# Overcurrent_Protection.net
KiCad netlist of a schematic drawn in Altium Designer
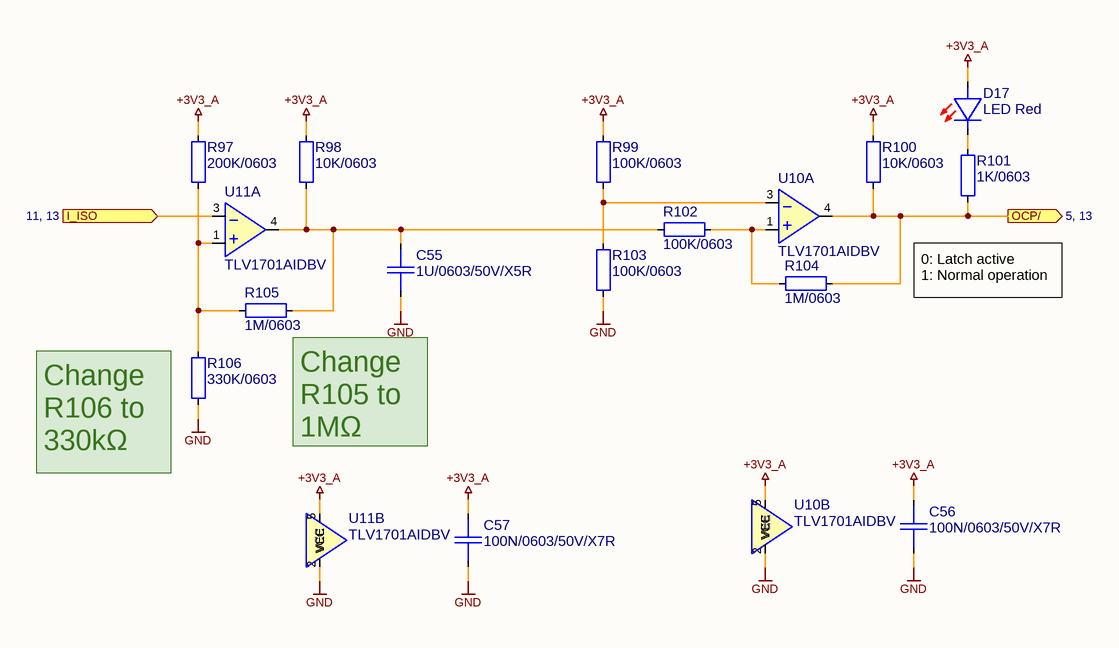
[diagram p0: Overcurrent_Protection.SchDoc]

(export (version "E")
  (design (tool "Eeschema 10.0.6"))
  (components
    (comp (ref "C55")
      (value "1U/0603/50V/X5R")
      (footprint "CAP0603_X7R")
      (description "CAP SM 0603 1.0uF 50V X5R")
      (fields (field (name "MANUFACTURER") "GENERIC"))
      (libsource (lib "daniw_altium_lib") (part "C"))
    )
    (comp (ref "C56")
      (value "100N/0603/50V/X7R")
      (footprint "CAP0603_X7R")
      (description "CAP SM 0603 100nF 50V X7R")
      (fields (field (name "MANUFACTURER") "GENERIC"))
      (libsource (lib "daniw_altium_lib") (part "C"))
    )
    (comp (ref "C57")
      (value "100N/0603/50V/X7R")
      (footprint "CAP0603_X7R")
      (description "CAP SM 0603 100nF 50V X7R")
      (fields (field (name "MANUFACTURER") "GENERIC"))
      (libsource (lib "daniw_altium_lib") (part "C"))
    )
    (comp (ref "D17")
      (value "LED Red")
      (footprint "LED0805_RED")
      (description "Generic LED Red 0805")
      (fields (field (name "PART NUMBER") "LED Red 0805") (field (name "MANUFACTURER") "GENERIC"))
      (libsource (lib "daniw_altium_lib") (part "LED_RED"))
    )
    (comp (ref "R97")
      (value "200K/0603")
      (footprint "R0603-0.40-WW")
      (description "RES SM 0603 200K")
      (fields (field (name "MANUFACTURER") "GENERIC"))
      (libsource (lib "daniw_altium_lib") (part "R"))
    )
    (comp (ref "R98")
      (value "10K/0603")
      (footprint "R0603-0.40-WW")
      (description "RES SM 0603 10K")
      (fields (field (name "MANUFACTURER") "GENERIC"))
      (libsource (lib "daniw_altium_lib") (part "R"))
    )
    (comp (ref "R99")
      (value "100K/0603")
      (footprint "R0603-0.40-WW")
      (description "RES SM 0603 100K")
      (fields (field (name "MANUFACTURER") "GENERIC"))
      (libsource (lib "daniw_altium_lib") (part "R"))
    )
    (comp (ref "R100")
      (value "10K/0603")
      (footprint "R0603-0.40-WW")
      (description "RES SM 0603 10K")
      (fields (field (name "MANUFACTURER") "GENERIC"))
      (libsource (lib "daniw_altium_lib") (part "R"))
    )
    (comp (ref "R101")
      (value "1K/0603")
      (footprint "R0603-0.40-WW")
      (description "RES SM 0603 1K")
      (fields (field (name "MANUFACTURER") "GENERIC"))
      (libsource (lib "daniw_altium_lib") (part "R"))
    )
    (comp (ref "R102")
      (value "100K/0603")
      (footprint "R0603-0.40-WW")
      (description "RES SM 0603 100K")
      (fields (field (name "MANUFACTURER") "GENERIC"))
      (libsource (lib "daniw_altium_lib") (part "R"))
    )
    (comp (ref "R103")
      (value "100K/0603")
      (footprint "R0603-0.40-WW")
      (description "RES SM 0603 100K")
      (fields (field (name "MANUFACTURER") "GENERIC"))
      (libsource (lib "daniw_altium_lib") (part "R"))
    )
    (comp (ref "R104")
      (value "1M/0603")
      (footprint "R0603-0.40-WW")
      (description "RES SM 0603 1M")
      (fields (field (name "MANUFACTURER") "GENERIC"))
      (libsource (lib "daniw_altium_lib") (part "R"))
    )
    (comp (ref "R105")
      (value "1M/0603")
      (footprint "R0603-0.40-WW")
      (description "RES SM 0603 1M")
      (fields (field (name "MANUFACTURER") "GENERIC"))
      (libsource (lib "daniw_altium_lib") (part "R"))
    )
    (comp (ref "R106")
      (value "330K/0603")
      (footprint "R0603-0.40-WW")
      (description "RES SM 0603 330K")
      (fields (field (name "MANUFACTURER") "GENERIC"))
      (libsource (lib "daniw_altium_lib") (part "R"))
    )
    (comp (ref "U10")
      (value "TLV1701AIDBV")
      (footprint "SOT2395P280X125-5-NW")
      (description "TLV1701 2.2-V to 36-V, microPower Comparato")
      (fields (field (name "PART NUMBER") "TLV1701 SOT23") (field (name "MANUFACTURER") "Texas Instruments"))
      (libsource (lib "daniw_altium_lib") (part "OPA_O4_P1_N3_VCC5_VEE2"))
    )
    (comp (ref "U11")
      (value "TLV1701AIDBV")
      (footprint "SOT2395P280X125-5-NW")
      (description "TLV1701 2.2-V to 36-V, microPower Comparato")
      (fields (field (name "PART NUMBER") "TLV1701 SOT23") (field (name "MANUFACTURER") "Texas Instruments"))
      (libsource (lib "daniw_altium_lib") (part "OPA_O4_P1_N3_VCC5_VEE2"))
    )
  )
  (nets
    (net (code "1") (name "+3V3_A") (class "Default")
      (node (ref "C56") (pin "1") (pinfunction "1_1") (pintype "passive"))
      (node (ref "C57") (pin "1") (pinfunction "1_1") (pintype "passive"))
      (node (ref "D17") (pin "2") (pinfunction "A_2") (pintype "passive"))
      (node (ref "R100") (pin "2") (pinfunction "2_2") (pintype "passive"))
      (node (ref "R97") (pin "1") (pinfunction "1_1") (pintype "passive"))
      (node (ref "R98") (pin "2") (pinfunction "2_2") (pintype "passive"))
      (node (ref "R99") (pin "2") (pinfunction "2_2") (pintype "passive"))
      (node (ref "U10") (pin "5") (pinfunction "VCC_5") (pintype "passive"))
      (node (ref "U11") (pin "5") (pinfunction "VCC_5") (pintype "passive"))
    )
    (net (code "2") (name "/I_ISO") (class "Default")
      (node (ref "U11") (pin "3") (pinfunction "IN-_3") (pintype "passive"))
    )
    (net (code "3") (name "/OCP{slash}") (class "Default")
      (node (ref "R100") (pin "1") (pinfunction "1_1") (pintype "passive"))
      (node (ref "R101") (pin "1") (pinfunction "1_1") (pintype "passive"))
      (node (ref "R104") (pin "2") (pinfunction "2_2") (pintype "passive"))
      (node (ref "U10") (pin "4") (pinfunction "OUT_4") (pintype "passive"))
    )
    (net (code "4") (name "GND") (class "Default")
      (node (ref "C55") (pin "2") (pinfunction "2_2") (pintype "passive"))
      (node (ref "C56") (pin "2") (pinfunction "2_2") (pintype "passive"))
      (node (ref "C57") (pin "2") (pinfunction "2_2") (pintype "passive"))
      (node (ref "R103") (pin "2") (pinfunction "2_2") (pintype "passive"))
      (node (ref "R106") (pin "2") (pinfunction "2_2") (pintype "passive"))
      (node (ref "U10") (pin "2") (pinfunction "VEE_2") (pintype "passive"))
      (node (ref "U11") (pin "2") (pinfunction "VEE_2") (pintype "passive"))
    )
    (net (code "5") (name "Net-(D17-C)") (class "Default")
      (node (ref "D17") (pin "1") (pinfunction "C_1") (pintype "passive"))
      (node (ref "R101") (pin "2") (pinfunction "2_2") (pintype "passive"))
    )
    (net (code "6") (name "Net-(U10A-IN+)") (class "Default")
      (node (ref "R102") (pin "2") (pinfunction "2_2") (pintype "passive"))
      (node (ref "R104") (pin "1") (pinfunction "1_1") (pintype "passive"))
      (node (ref "U10") (pin "1") (pinfunction "IN+_1") (pintype "passive"))
    )
    (net (code "7") (name "Net-(U10A-IN-)") (class "Default")
      (node (ref "R103") (pin "1") (pinfunction "1_1") (pintype "passive"))
      (node (ref "R99") (pin "1") (pinfunction "1_1") (pintype "passive"))
      (node (ref "U10") (pin "3") (pinfunction "IN-_3") (pintype "passive"))
    )
    (net (code "8") (name "Net-(U11A-IN+)") (class "Default")
      (node (ref "R105") (pin "1") (pinfunction "1_1") (pintype "passive"))
      (node (ref "R106") (pin "1") (pinfunction "1_1") (pintype "passive"))
      (node (ref "R97") (pin "2") (pinfunction "2_2") (pintype "passive"))
      (node (ref "U11") (pin "1") (pinfunction "IN+_1") (pintype "passive"))
    )
    (net (code "9") (name "Net-(U11A-OUT)") (class "Default")
      (node (ref "C55") (pin "1") (pinfunction "1_1") (pintype "passive"))
      (node (ref "R102") (pin "1") (pinfunction "1_1") (pintype "passive"))
      (node (ref "R105") (pin "2") (pinfunction "2_2") (pintype "passive"))
      (node (ref "R98") (pin "1") (pinfunction "1_1") (pintype "passive"))
      (node (ref "U11") (pin "4") (pinfunction "OUT_4") (pintype "passive"))
    )
  )
)
